# 04_SRAD_Ejection_Charges_SchDoc.net
KiCad netlist of a schematic drawn in Altium Designer
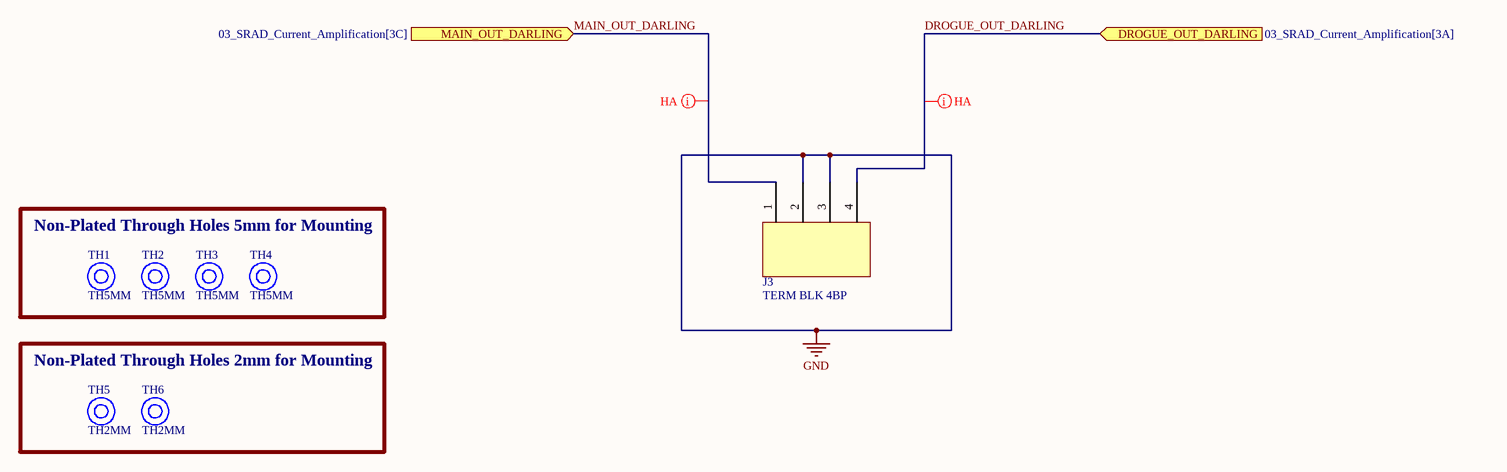
[diagram p0: 04_SRAD_Ejection_Charges.SchDoc.SchDoc]

(export (version "E")
  (design (tool "Eeschema 10.0.6"))
  (components
    (comp (ref "J3")
      (value "TERM BLK 4BP")
      (footprint "PCB TERM BLK 4P 2.54MM")
      (fields
        (field (name "MANUFACTURER") "TE Connectivity")
        (field (name "MANUFACTURER PART NUMBER") "282834-4")
        (field (name "VOLTAGE") "150V")
      )
      (libsource (lib "SRAD_SAC_Schlib") (part "PCB TERM BLK 4P 2.54MM"))
    )
    (comp (ref "TH1")
      (value "TH5MM")
      (footprint "Mounting Hole Non-Plated")
      (description "Non-plated THT 5mm diameter")
      (libsource (lib "SRAD_SAC_Schlib") (part "Mounting Hole Non-Plated"))
    )
    (comp (ref "TH2")
      (value "TH5MM")
      (footprint "Mounting Hole Non-Plated")
      (description "Non-plated THT 5mm diameter")
      (libsource (lib "SRAD_SAC_Schlib") (part "Mounting Hole Non-Plated"))
    )
    (comp (ref "TH3")
      (value "TH5MM")
      (footprint "Mounting Hole Non-Plated")
      (description "Non-plated THT 5mm diameter")
      (libsource (lib "SRAD_SAC_Schlib") (part "Mounting Hole Non-Plated"))
    )
    (comp (ref "TH4")
      (value "TH5MM")
      (footprint "Mounting Hole Non-Plated")
      (description "Non-plated THT 5mm diameter")
      (libsource (lib "SRAD_SAC_Schlib") (part "Mounting Hole Non-Plated"))
    )
    (comp (ref "TH5")
      (value "TH2MM")
      (footprint "Mounting Hole Non-Plated 2MM")
      (description "Non-plated THT 2mm diameter")
      (libsource (lib "SRAD_SAC_Schlib") (part "Mounting Hole Non-Plated 2mm"))
    )
    (comp (ref "TH6")
      (value "TH2MM")
      (footprint "Mounting Hole Non-Plated 2MM")
      (description "Non-plated THT 2mm diameter")
      (libsource (lib "SRAD_SAC_Schlib") (part "Mounting Hole Non-Plated 2mm"))
    )
  )
  (nets
    (net (code "1") (name "/DROGUE_OUT_DARLING") (class "Default")
      (node (ref "J3") (pin "4") (pinfunction "4_4") (pintype "passive"))
    )
    (net (code "2") (name "/MAIN_OUT_DARLING") (class "Default")
      (node (ref "J3") (pin "1") (pinfunction "1_1") (pintype "passive"))
    )
    (net (code "3") (name "GND") (class "Default")
      (node (ref "J3") (pin "2") (pinfunction "2_2") (pintype "passive"))
      (node (ref "J3") (pin "3") (pinfunction "3_3") (pintype "passive"))
    )
  )
)
